# DAUGHTER_SENSOR.net
KiCad netlist of a schematic drawn in EAGLE
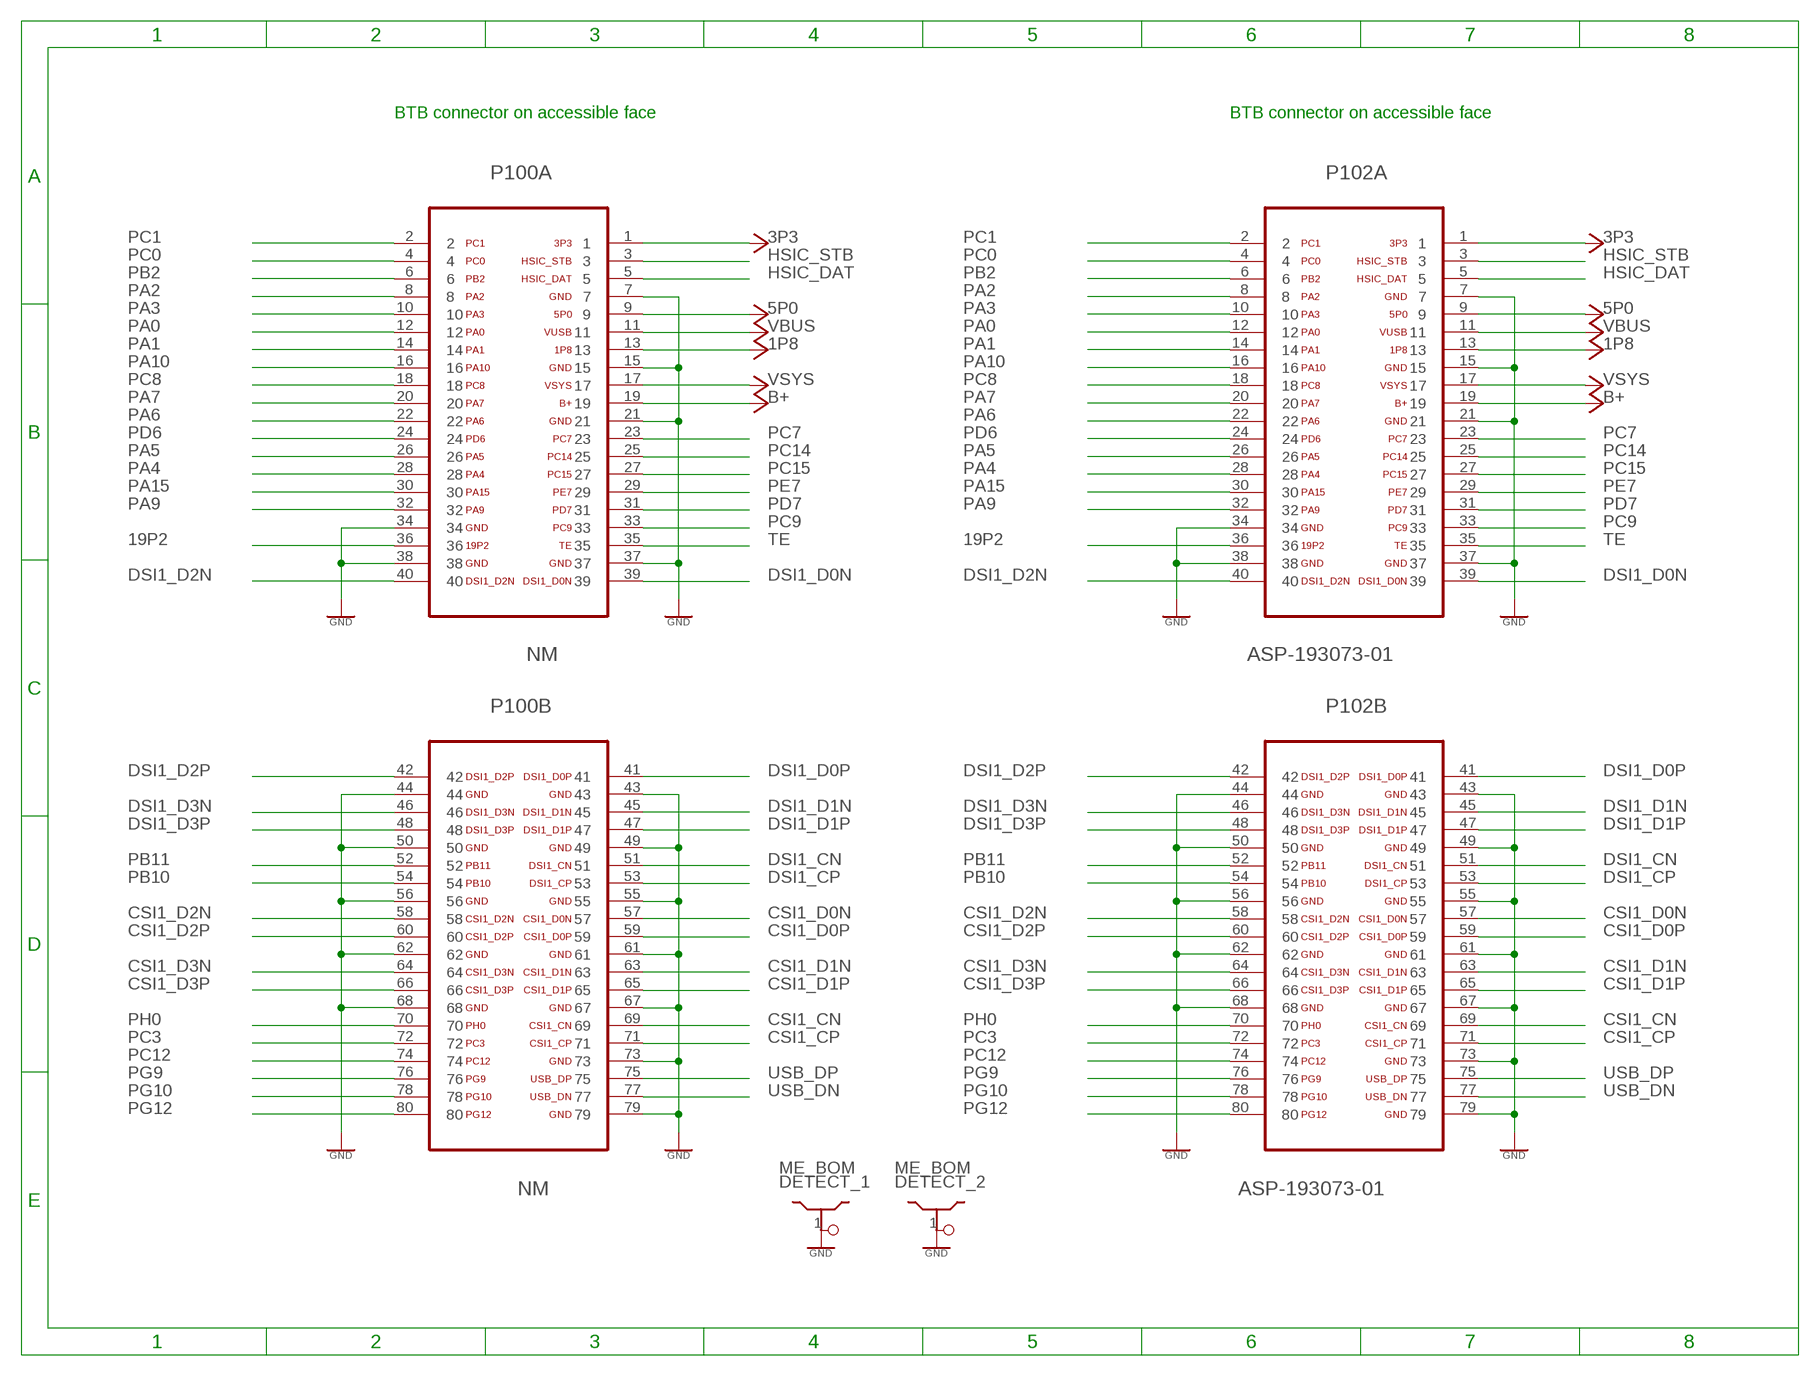
[diagram p0: schematic, sheet 1]
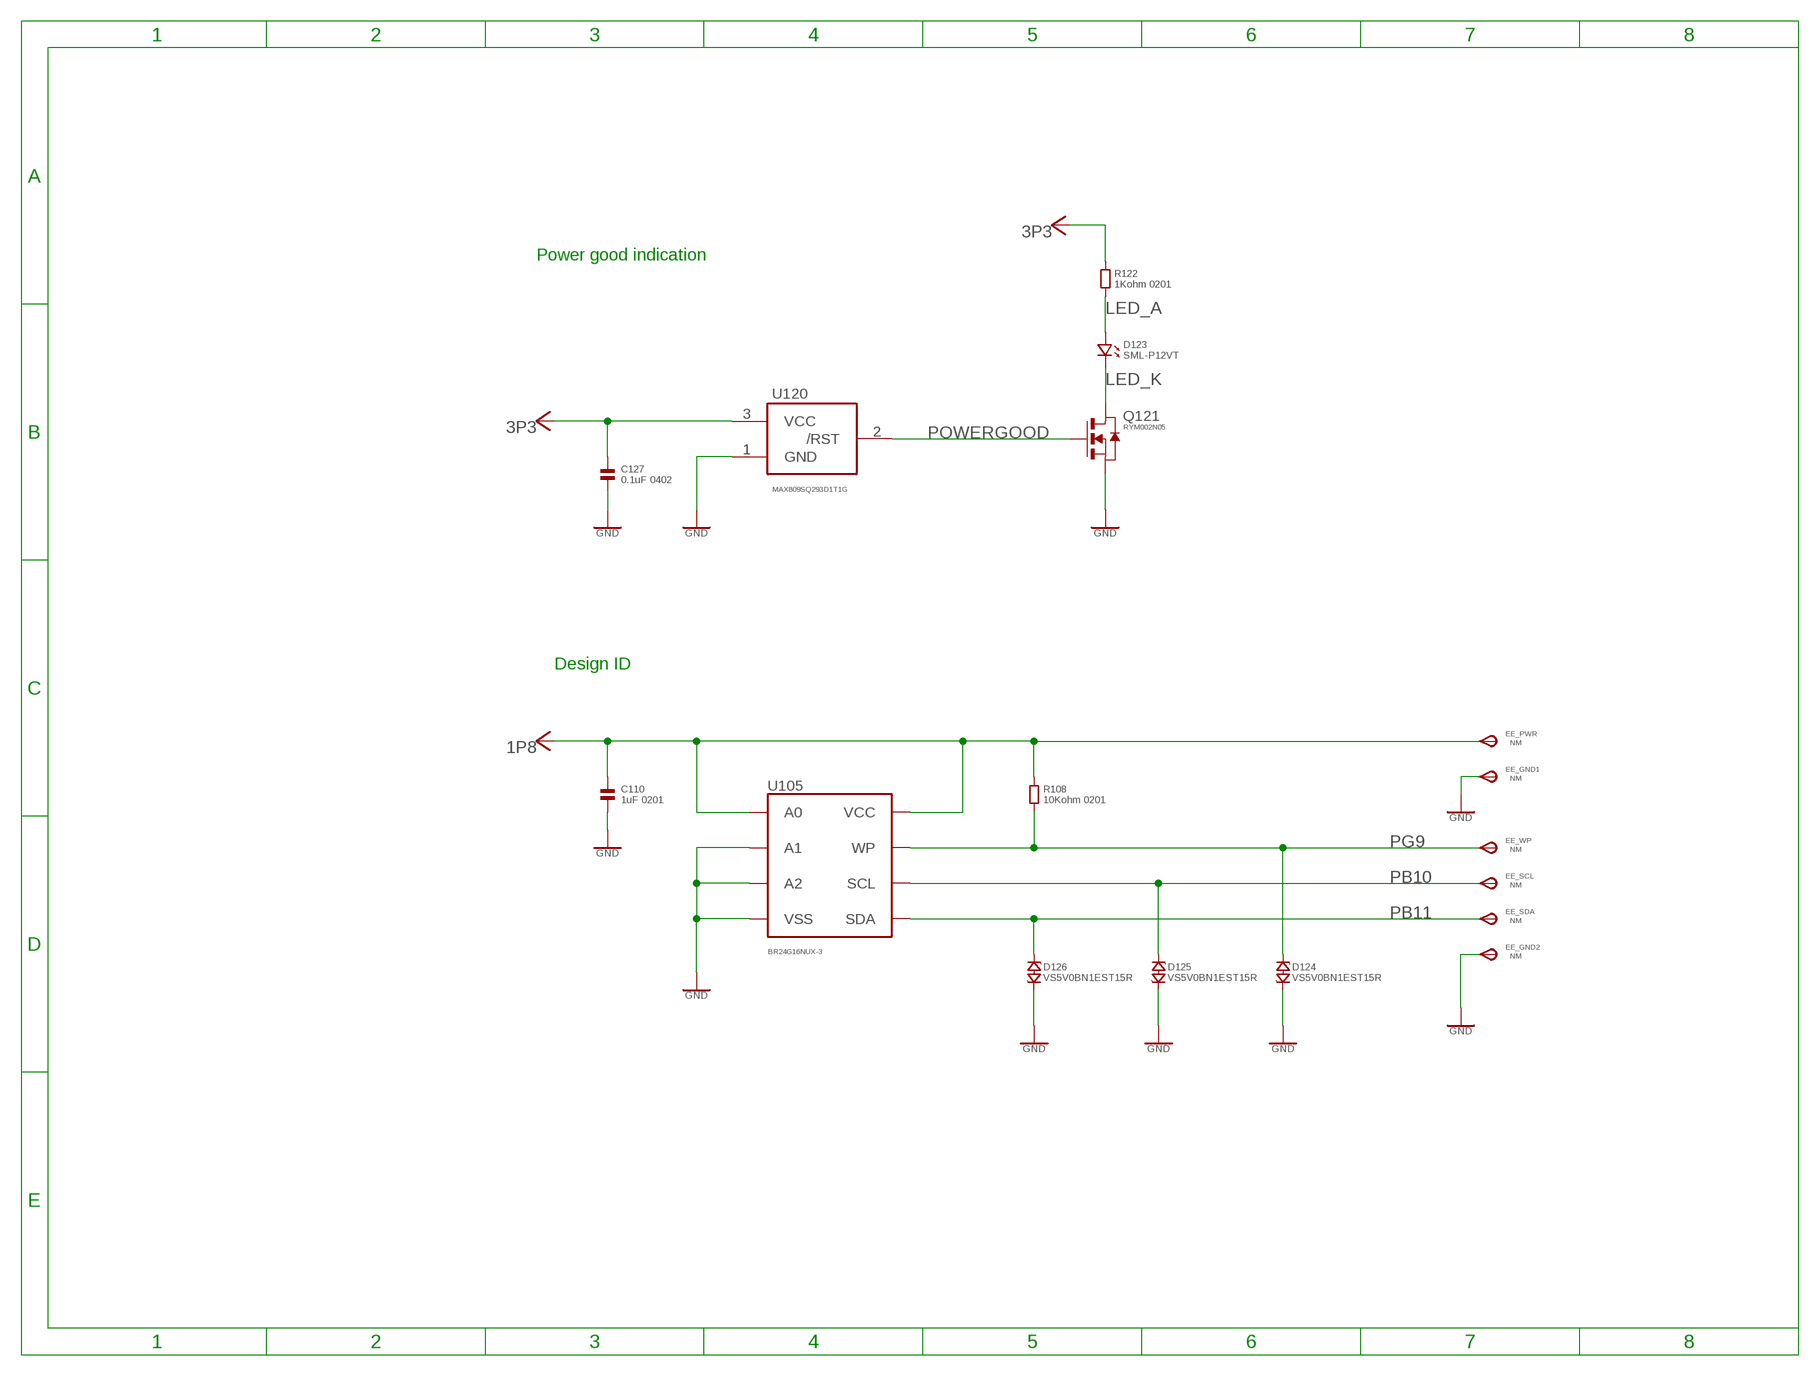
[diagram p1: schematic, sheet 2]
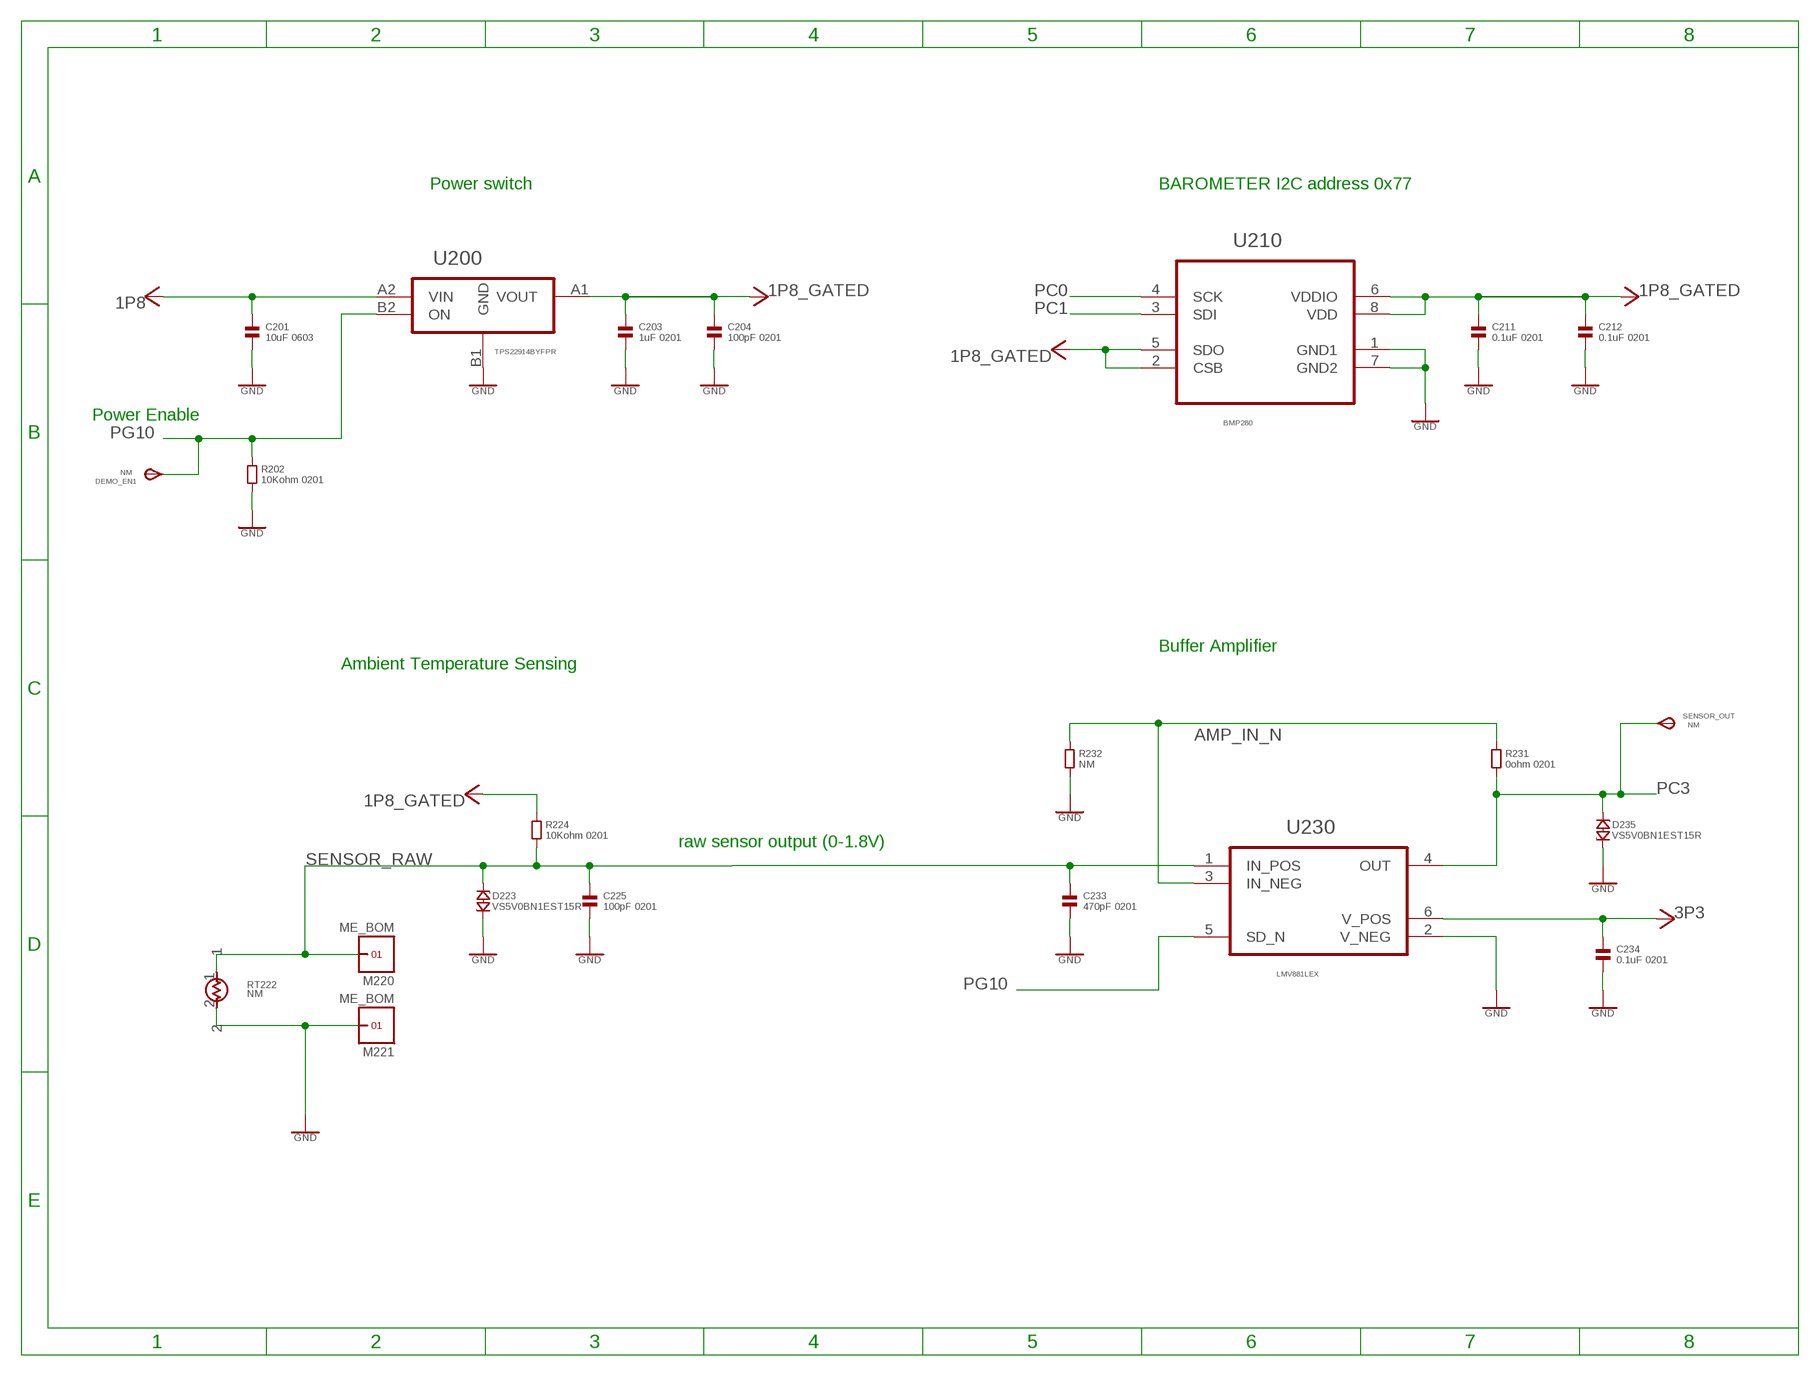
[diagram p2: schematic, sheet 3]

(export (version "E")
  (design (tool "Eeschema 10.0.6"))
  (components
    (comp (ref "C110")
      (value "1uF 0201")
      (footprint "eagle-import:0201")
      (libsource (lib "eagle-import") (part "CAPACITOR.0201"))
    )
    (comp (ref "C127")
      (value "0.1uF 0402")
      (footprint "eagle-import:0402")
      (libsource (lib "eagle-import") (part "CAPACITOR.0402"))
    )
    (comp (ref "D123")
      (value "SML-P12VT")
      (footprint "eagle-import:0503.LED")
      (libsource (lib "eagle-import") (part "LED.0503"))
    )
    (comp (ref "D124")
      (value "VS5V0BN1EST15R")
      (footprint "eagle-import:CHIP_0201")
      (libsource (lib "eagle-import") (part "ESD_VARISTOR.0201"))
    )
    (comp (ref "D125")
      (value "VS5V0BN1EST15R")
      (footprint "eagle-import:CHIP_0201")
      (libsource (lib "eagle-import") (part "ESD_VARISTOR.0201"))
    )
    (comp (ref "D126")
      (value "VS5V0BN1EST15R")
      (footprint "eagle-import:CHIP_0201")
      (libsource (lib "eagle-import") (part "ESD_VARISTOR.0201"))
    )
    (comp (ref "EE_GND1")
      (value "NM")
      (footprint "eagle-import:TP11R")
      (libsource (lib "eagle-import") (part "TPSTP11R"))
    )
    (comp (ref "EE_GND2")
      (value "NM")
      (footprint "eagle-import:TP11R")
      (libsource (lib "eagle-import") (part "TPSTP11R"))
    )
    (comp (ref "EE_PWR")
      (value "NM")
      (footprint "eagle-import:TP11R")
      (libsource (lib "eagle-import") (part "TPSTP11R"))
    )
    (comp (ref "EE_SCL")
      (value "NM")
      (footprint "eagle-import:TP11R")
      (libsource (lib "eagle-import") (part "TPSTP11R"))
    )
    (comp (ref "EE_SDA")
      (value "NM")
      (footprint "eagle-import:TP11R")
      (libsource (lib "eagle-import") (part "TPSTP11R"))
    )
    (comp (ref "EE_WP")
      (value "NM")
      (footprint "eagle-import:TP11R")
      (libsource (lib "eagle-import") (part "TPSTP11R"))
    )
    (comp (ref "Q121")
      (value "RYM002N05")
      (footprint "eagle-import:VMT3")
      (libsource (lib "eagle-import") (part "FET-NRYM002N05"))
    )
    (comp (ref "R108")
      (value "10Kohm 0201")
      (footprint "eagle-import:0201")
      (libsource (lib "eagle-import") (part "RESISTOR.0201"))
    )
    (comp (ref "R122")
      (value "1Kohm 0201")
      (footprint "eagle-import:0201")
      (libsource (lib "eagle-import") (part "RESISTOR.0201"))
    )
    (comp (ref "U105")
      (value "BR24G16NUX-3")
      (footprint "eagle-import:DFN-8")
      (libsource (lib "eagle-import") (part "EEPROMDFN8"))
    )
    (comp (ref "U120")
      (value "MAX809SQ293D1T1G")
      (footprint "eagle-import:SC70-3L")
      (fields (field (name "MPN") "MAX809SQ293D1T1"))
      (libsource (lib "eagle-import") (part "MAX809"))
    )
    (comp (ref "DETECT_1")
      (value "ME_BOM")
      (footprint "eagle-import:PLUG")
      (fields (field (name "MPN") "refer to ME BOM"))
      (libsource (lib "eagle-import") (part "SHIELDDETECT"))
    )
    (comp (ref "DETECT_2")
      (value "ME_BOM")
      (footprint "eagle-import:PLUG")
      (fields (field (name "MPN") "refer to ME BOM"))
      (libsource (lib "eagle-import") (part "SHIELDDETECT"))
    )
    (comp (ref "P100")
      (value "NM")
      (footprint "eagle-import:CLM-140-02-L-D-K_GOLD")
      (fields (field (name "MPN") "CLM-140-02-L-D-K"))
      (libsource (lib "eagle-import") (part "CLM-140-02-L-D-KGOLD"))
    )
    (comp (ref "P102")
      (value "ASP-193073-01")
      (footprint "eagle-import:FTMH-140-02-L-DV-ES-P-TR")
      (fields (field (name "MPN") "ASP-193073-01"))
      (libsource (lib "eagle-import") (part "FTMH-140-02-L-DV-ES-P-TR"))
    )
    (comp (ref "C201")
      (value "10uF 0603")
      (footprint "eagle-import:0603")
      (libsource (lib "eagle-import") (part "CAPACITOR.0603"))
    )
    (comp (ref "C203")
      (value "1uF 0201")
      (footprint "eagle-import:0201")
      (libsource (lib "eagle-import") (part "CAPACITOR.0201"))
    )
    (comp (ref "C204")
      (value "100pF 0201")
      (footprint "eagle-import:0201")
      (libsource (lib "eagle-import") (part "CAPACITOR.0201"))
    )
    (comp (ref "C211")
      (value "0.1uF 0201")
      (footprint "eagle-import:0201")
      (libsource (lib "eagle-import") (part "CAPACITOR.0201"))
    )
    (comp (ref "C212")
      (value "0.1uF 0201")
      (footprint "eagle-import:0201")
      (libsource (lib "eagle-import") (part "CAPACITOR.0201"))
    )
    (comp (ref "C225")
      (value "100pF 0201")
      (footprint "eagle-import:0201")
      (libsource (lib "eagle-import") (part "CAPACITOR.0201"))
    )
    (comp (ref "C233")
      (value "470pF 0201")
      (footprint "eagle-import:0201")
      (libsource (lib "eagle-import") (part "CAPACITOR.0201"))
    )
    (comp (ref "C234")
      (value "0.1uF 0201")
      (footprint "eagle-import:0201")
      (libsource (lib "eagle-import") (part "CAPACITOR.0201"))
    )
    (comp (ref "D223")
      (value "VS5V0BN1EST15R")
      (footprint "eagle-import:CHIP_0201")
      (libsource (lib "eagle-import") (part "ESD_VARISTOR.0201"))
    )
    (comp (ref "D235")
      (value "VS5V0BN1EST15R")
      (footprint "eagle-import:CHIP_0201")
      (libsource (lib "eagle-import") (part "ESD_VARISTOR.0201"))
    )
    (comp (ref "DEMO_EN1")
      (value "NM")
      (footprint "eagle-import:TP11R")
      (libsource (lib "eagle-import") (part "TPSTP11R"))
    )
    (comp (ref "M220")
      (value "ME_BOM")
      (footprint "eagle-import:UNIVERSAL_CONTACT")
      (fields (field (name "MPN") "refer to ME BOM"))
      (libsource (lib "eagle-import") (part "UNVERSA_CONTACT"))
    )
    (comp (ref "M221")
      (value "ME_BOM")
      (footprint "eagle-import:UNIVERSAL_CONTACT")
      (fields (field (name "MPN") "refer to ME BOM"))
      (libsource (lib "eagle-import") (part "UNVERSA_CONTACT"))
    )
    (comp (ref "R202")
      (value "10Kohm 0201")
      (footprint "eagle-import:0201")
      (libsource (lib "eagle-import") (part "RESISTOR.0201"))
    )
    (comp (ref "R224")
      (value "10Kohm 0201")
      (footprint "eagle-import:0201")
      (libsource (lib "eagle-import") (part "RESISTOR.0201"))
    )
    (comp (ref "R231")
      (value "0ohm 0201")
      (footprint "eagle-import:0201")
      (libsource (lib "eagle-import") (part "RESISTOR.0201"))
    )
    (comp (ref "R232")
      (value "NM")
      (footprint "eagle-import:0201")
      (libsource (lib "eagle-import") (part "RESISTOR.0201"))
    )
    (comp (ref "RT222")
      (value "NM")
      (footprint "eagle-import:0201")
      (fields (field (name "MPN") "NCP03XV103XV103E05RL/NTCG0603UH103HT"))
      (libsource (lib "eagle-import") (part "THERMISTOR"))
    )
    (comp (ref "SENSOR_OUT")
      (value "NM")
      (footprint "eagle-import:TP11R")
      (libsource (lib "eagle-import") (part "TPSTP11R"))
    )
    (comp (ref "U200")
      (value "TPS22914BYFPR")
      (footprint "eagle-import:BGA0_75SQ_PS0_4_P4")
      (libsource (lib "eagle-import") (part "TPS22914BYFPR"))
    )
    (comp (ref "U210")
      (value "BMP280")
      (footprint "eagle-import:LGA2X2_5PS0_65_P8")
      (libsource (lib "eagle-import") (part "BMP280"))
    )
    (comp (ref "U230")
      (value "LMV881LEX")
      (footprint "eagle-import:DFN1_5X1PS0_5P6")
      (libsource (lib "eagle-import") (part "LMV881LEX"))
    )
  )
  (nets
    (net (code "1") (name "1P8") (class "Default")
      (node (ref "C110") (pin "1") (pinfunction "1_1") (pintype "bidirectional"))
      (node (ref "C201") (pin "1") (pinfunction "1_1") (pintype "bidirectional"))
      (node (ref "EE_PWR") (pin "TP") (pinfunction "PP_TP") (pintype "input"))
      (node (ref "P100") (pin "13") (pinfunction "13_13") (pintype "passive"))
      (node (ref "P102") (pin "13") (pinfunction "13_13") (pintype "passive"))
      (node (ref "R108") (pin "1") (pinfunction "1_1") (pintype "bidirectional"))
      (node (ref "U105") (pin "P$1") (pinfunction "A0_P$1") (pintype "input"))
      (node (ref "U105") (pin "P$8") (pinfunction "VCC_P$8") (pintype "power_in"))
      (node (ref "U200") (pin "A2") (pinfunction "VIN_A2") (pintype "power_in"))
    )
    (net (code "2") (name "1P8_GATED") (class "Default")
      (node (ref "C203") (pin "1") (pinfunction "1_1") (pintype "bidirectional"))
      (node (ref "C204") (pin "1") (pinfunction "1_1") (pintype "bidirectional"))
      (node (ref "C211") (pin "1") (pinfunction "1_1") (pintype "bidirectional"))
      (node (ref "C212") (pin "1") (pinfunction "1_1") (pintype "bidirectional"))
      (node (ref "R224") (pin "1") (pinfunction "1_1") (pintype "bidirectional"))
      (node (ref "U200") (pin "A1") (pinfunction "VOUT_A1") (pintype "power_in"))
      (node (ref "U210") (pin "2") (pinfunction "CSB_2") (pintype "input"))
      (node (ref "U210") (pin "5") (pinfunction "SDO_5") (pintype "bidirectional"))
      (node (ref "U210") (pin "6") (pinfunction "VDDIO_6") (pintype "power_in"))
      (node (ref "U210") (pin "8") (pinfunction "VDD_8") (pintype "power_in"))
    )
    (net (code "3") (name "3P3") (class "Default")
      (node (ref "C127") (pin "1") (pinfunction "1_1") (pintype "bidirectional"))
      (node (ref "C234") (pin "1") (pinfunction "1_1") (pintype "bidirectional"))
      (node (ref "P100") (pin "1") (pinfunction "1_1") (pintype "passive"))
      (node (ref "P102") (pin "1") (pinfunction "1_1") (pintype "passive"))
      (node (ref "R122") (pin "1") (pinfunction "1_1") (pintype "bidirectional"))
      (node (ref "U120") (pin "3") (pinfunction "VCC_3") (pintype "input"))
      (node (ref "U230") (pin "6") (pinfunction "V_POS_6") (pintype "power_in"))
    )
    (net (code "4") (name "5P0") (class "Default")
      (node (ref "P100") (pin "9") (pinfunction "9_9") (pintype "passive"))
      (node (ref "P102") (pin "9") (pinfunction "9_9") (pintype "passive"))
    )
    (net (code "5") (name "19P2") (class "Default")
      (node (ref "P100") (pin "36") (pinfunction "36_36") (pintype "passive"))
      (node (ref "P102") (pin "36") (pinfunction "36_36") (pintype "passive"))
    )
    (net (code "6") (name "AMP_IN_N") (class "Default")
      (node (ref "R231") (pin "1") (pinfunction "1_1") (pintype "bidirectional"))
      (node (ref "R232") (pin "1") (pinfunction "1_1") (pintype "bidirectional"))
      (node (ref "U230") (pin "3") (pinfunction "IN_NEG_3") (pintype "input"))
    )
    (net (code "7") (name "B+") (class "Default")
      (node (ref "P100") (pin "19") (pinfunction "19_19") (pintype "passive"))
      (node (ref "P102") (pin "19") (pinfunction "19_19") (pintype "passive"))
    )
    (net (code "8") (name "CSI1_CN") (class "Default")
      (node (ref "P100") (pin "69") (pinfunction "69_69") (pintype "passive"))
      (node (ref "P102") (pin "69") (pinfunction "69_69") (pintype "passive"))
    )
    (net (code "9") (name "CSI1_CP") (class "Default")
      (node (ref "P100") (pin "71") (pinfunction "71_71") (pintype "passive"))
      (node (ref "P102") (pin "71") (pinfunction "71_71") (pintype "passive"))
    )
    (net (code "10") (name "CSI1_D0N") (class "Default")
      (node (ref "P100") (pin "57") (pinfunction "57_57") (pintype "passive"))
      (node (ref "P102") (pin "57") (pinfunction "57_57") (pintype "passive"))
    )
    (net (code "11") (name "CSI1_D0P") (class "Default")
      (node (ref "P100") (pin "59") (pinfunction "59_59") (pintype "passive"))
      (node (ref "P102") (pin "59") (pinfunction "59_59") (pintype "passive"))
    )
    (net (code "12") (name "CSI1_D1N") (class "Default")
      (node (ref "P100") (pin "63") (pinfunction "63_63") (pintype "passive"))
      (node (ref "P102") (pin "63") (pinfunction "63_63") (pintype "passive"))
    )
    (net (code "13") (name "CSI1_D1P") (class "Default")
      (node (ref "P100") (pin "65") (pinfunction "65_65") (pintype "passive"))
      (node (ref "P102") (pin "65") (pinfunction "65_65") (pintype "passive"))
    )
    (net (code "14") (name "CSI1_D2N") (class "Default")
      (node (ref "P100") (pin "58") (pinfunction "58_58") (pintype "passive"))
      (node (ref "P102") (pin "58") (pinfunction "58_58") (pintype "passive"))
    )
    (net (code "15") (name "CSI1_D2P") (class "Default")
      (node (ref "P100") (pin "60") (pinfunction "60_60") (pintype "passive"))
      (node (ref "P102") (pin "60") (pinfunction "60_60") (pintype "passive"))
    )
    (net (code "16") (name "CSI1_D3N") (class "Default")
      (node (ref "P100") (pin "64") (pinfunction "64_64") (pintype "passive"))
      (node (ref "P102") (pin "64") (pinfunction "64_64") (pintype "passive"))
    )
    (net (code "17") (name "CSI1_D3P") (class "Default")
      (node (ref "P100") (pin "66") (pinfunction "66_66") (pintype "passive"))
      (node (ref "P102") (pin "66") (pinfunction "66_66") (pintype "passive"))
    )
    (net (code "18") (name "DSI1_CN") (class "Default")
      (node (ref "P100") (pin "51") (pinfunction "51_51") (pintype "passive"))
      (node (ref "P102") (pin "51") (pinfunction "51_51") (pintype "passive"))
    )
    (net (code "19") (name "DSI1_CP") (class "Default")
      (node (ref "P100") (pin "53") (pinfunction "53_53") (pintype "passive"))
      (node (ref "P102") (pin "53") (pinfunction "53_53") (pintype "passive"))
    )
    (net (code "20") (name "DSI1_D0N") (class "Default")
      (node (ref "P100") (pin "39") (pinfunction "39_39") (pintype "passive"))
      (node (ref "P102") (pin "39") (pinfunction "39_39") (pintype "passive"))
    )
    (net (code "21") (name "DSI1_D0P") (class "Default")
      (node (ref "P100") (pin "41") (pinfunction "41_41") (pintype "passive"))
      (node (ref "P102") (pin "41") (pinfunction "41_41") (pintype "passive"))
    )
    (net (code "22") (name "DSI1_D1N") (class "Default")
      (node (ref "P100") (pin "45") (pinfunction "45_45") (pintype "passive"))
      (node (ref "P102") (pin "45") (pinfunction "45_45") (pintype "passive"))
    )
    (net (code "23") (name "DSI1_D1P") (class "Default")
      (node (ref "P100") (pin "47") (pinfunction "47_47") (pintype "passive"))
      (node (ref "P102") (pin "47") (pinfunction "47_47") (pintype "passive"))
    )
    (net (code "24") (name "DSI1_D2N") (class "Default")
      (node (ref "P100") (pin "40") (pinfunction "40_40") (pintype "passive"))
      (node (ref "P102") (pin "40") (pinfunction "40_40") (pintype "passive"))
    )
    (net (code "25") (name "DSI1_D2P") (class "Default")
      (node (ref "P100") (pin "42") (pinfunction "42_42") (pintype "passive"))
      (node (ref "P102") (pin "42") (pinfunction "42_42") (pintype "passive"))
    )
    (net (code "26") (name "DSI1_D3N") (class "Default")
      (node (ref "P100") (pin "46") (pinfunction "46_46") (pintype "passive"))
      (node (ref "P102") (pin "46") (pinfunction "46_46") (pintype "passive"))
    )
    (net (code "27") (name "DSI1_D3P") (class "Default")
      (node (ref "P100") (pin "48") (pinfunction "48_48") (pintype "passive"))
      (node (ref "P102") (pin "48") (pinfunction "48_48") (pintype "passive"))
    )
    (net (code "28") (name "GND") (class "Default")
      (node (ref "C110") (pin "2") (pinfunction "2_2") (pintype "bidirectional"))
      (node (ref "C127") (pin "2") (pinfunction "2_2") (pintype "bidirectional"))
      (node (ref "C201") (pin "2") (pinfunction "2_2") (pintype "bidirectional"))
      (node (ref "C203") (pin "2") (pinfunction "2_2") (pintype "bidirectional"))
      (node (ref "C204") (pin "2") (pinfunction "2_2") (pintype "bidirectional"))
      (node (ref "C211") (pin "2") (pinfunction "2_2") (pintype "bidirectional"))
      (node (ref "C212") (pin "2") (pinfunction "2_2") (pintype "bidirectional"))
      (node (ref "C225") (pin "2") (pinfunction "2_2") (pintype "bidirectional"))
      (node (ref "C233") (pin "2") (pinfunction "2_2") (pintype "bidirectional"))
      (node (ref "C234") (pin "2") (pinfunction "2_2") (pintype "bidirectional"))
      (node (ref "D124") (pin "P$2") (pinfunction "2_P$2") (pintype "bidirectional"))
      (node (ref "D125") (pin "P$2") (pinfunction "2_P$2") (pintype "bidirectional"))
      (node (ref "D126") (pin "P$2") (pinfunction "2_P$2") (pintype "bidirectional"))
      (node (ref "D223") (pin "P$2") (pinfunction "2_P$2") (pintype "bidirectional"))
      (node (ref "D235") (pin "P$2") (pinfunction "2_P$2") (pintype "bidirectional"))
      (node (ref "DETECT_1") (pin "1") (pinfunction "1_1") (pintype "passive"))
      (node (ref "DETECT_2") (pin "1") (pinfunction "1_1") (pintype "passive"))
      (node (ref "EE_GND1") (pin "TP") (pinfunction "PP_TP") (pintype "input"))
      (node (ref "EE_GND2") (pin "TP") (pinfunction "PP_TP") (pintype "input"))
      (node (ref "M221") (pin "G1") (pinfunction "1_G1") (pintype "bidirectional"))
      (node (ref "P100") (pin "15") (pinfunction "15_15") (pintype "passive"))
      (node (ref "P100") (pin "21") (pinfunction "21_21") (pintype "passive"))
      (node (ref "P100") (pin "34") (pinfunction "34_34") (pintype "passive"))
      (node (ref "P100") (pin "37") (pinfunction "37_37") (pintype "passive"))
      (node (ref "P100") (pin "38") (pinfunction "38_38") (pintype "passive"))
      (node (ref "P100") (pin "43") (pinfunction "43_43") (pintype "passive"))
      (node (ref "P100") (pin "44") (pinfunction "44_44") (pintype "passive"))
      (node (ref "P100") (pin "49") (pinfunction "49_49") (pintype "passive"))
      (node (ref "P100") (pin "50") (pinfunction "50_50") (pintype "passive"))
      (node (ref "P100") (pin "55") (pinfunction "55_55") (pintype "passive"))
      (node (ref "P100") (pin "56") (pinfunction "56_56") (pintype "passive"))
      (node (ref "P100") (pin "61") (pinfunction "61_61") (pintype "passive"))
      (node (ref "P100") (pin "62") (pinfunction "62_62") (pintype "passive"))
      (node (ref "P100") (pin "67") (pinfunction "67_67") (pintype "passive"))
      (node (ref "P100") (pin "68") (pinfunction "68_68") (pintype "passive"))
      (node (ref "P100") (pin "7") (pinfunction "7_7") (pintype "passive"))
      (node (ref "P100") (pin "73") (pinfunction "73_73") (pintype "passive"))
      (node (ref "P100") (pin "79") (pinfunction "79_79") (pintype "passive"))
      (node (ref "P102") (pin "15") (pinfunction "15_15") (pintype "passive"))
      (node (ref "P102") (pin "21") (pinfunction "21_21") (pintype "passive"))
      (node (ref "P102") (pin "34") (pinfunction "34_34") (pintype "passive"))
      (node (ref "P102") (pin "37") (pinfunction "37_37") (pintype "passive"))
      (node (ref "P102") (pin "38") (pinfunction "38_38") (pintype "passive"))
      (node (ref "P102") (pin "43") (pinfunction "43_43") (pintype "passive"))
      (node (ref "P102") (pin "44") (pinfunction "44_44") (pintype "passive"))
      (node (ref "P102") (pin "49") (pinfunction "49_49") (pintype "passive"))
      (node (ref "P102") (pin "50") (pinfunction "50_50") (pintype "passive"))
      (node (ref "P102") (pin "55") (pinfunction "55_55") (pintype "passive"))
      (node (ref "P102") (pin "56") (pinfunction "56_56") (pintype "passive"))
      (node (ref "P102") (pin "61") (pinfunction "61_61") (pintype "passive"))
      (node (ref "P102") (pin "62") (pinfunction "62_62") (pintype "passive"))
      (node (ref "P102") (pin "67") (pinfunction "67_67") (pintype "passive"))
      (node (ref "P102") (pin "68") (pinfunction "68_68") (pintype "passive"))
      (node (ref "P102") (pin "7") (pinfunction "7_7") (pintype "passive"))
      (node (ref "P102") (pin "73") (pinfunction "73_73") (pintype "passive"))
      (node (ref "P102") (pin "79") (pinfunction "79_79") (pintype "passive"))
      (node (ref "Q121") (pin "2") (pinfunction "S_2") (pintype "passive"))
      (node (ref "R202") (pin "2") (pinfunction "2_2") (pintype "bidirectional"))
      (node (ref "R232") (pin "2") (pinfunction "2_2") (pintype "bidirectional"))
      (node (ref "RT222") (pin "2") (pinfunction "2_2") (pintype "bidirectional"))
      (node (ref "U105") (pin "P$2") (pinfunction "A1_P$2") (pintype "input"))
      (node (ref "U105") (pin "P$3") (pinfunction "A2_P$3") (pintype "input"))
      (node (ref "U105") (pin "P$4") (pinfunction "VSS_P$4") (pintype "power_in"))
      (node (ref "U105") (pin "P$9") (pinfunction "VSS_P$9") (pintype "power_in"))
      (node (ref "U120") (pin "1") (pinfunction "GND_1") (pintype "power_in"))
      (node (ref "U200") (pin "B1") (pinfunction "GND_B1") (pintype "power_in"))
      (node (ref "U210") (pin "1") (pinfunction "GND1_1") (pintype "power_in"))
      (node (ref "U210") (pin "7") (pinfunction "GND2_7") (pintype "power_in"))
      (node (ref "U230") (pin "2") (pinfunction "V_NEG_2") (pintype "power_in"))
    )
    (net (code "29") (name "HSIC_DAT") (class "Default")
      (node (ref "P100") (pin "5") (pinfunction "5_5") (pintype "passive"))
      (node (ref "P102") (pin "5") (pinfunction "5_5") (pintype "passive"))
    )
    (net (code "30") (name "HSIC_STB") (class "Default")
      (node (ref "P100") (pin "3") (pinfunction "3_3") (pintype "passive"))
      (node (ref "P102") (pin "3") (pinfunction "3_3") (pintype "passive"))
    )
    (net (code "31") (name "LED_A") (class "Default")
      (node (ref "D123") (pin "P$1") (pinfunction "1_P$1") (pintype "bidirectional"))
      (node (ref "R122") (pin "2") (pinfunction "2_2") (pintype "bidirectional"))
    )
    (net (code "32") (name "LED_K") (class "Default")
      (node (ref "D123") (pin "P$2") (pinfunction "2_P$2") (pintype "bidirectional"))
      (node (ref "Q121") (pin "3") (pinfunction "D_3") (pintype "passive"))
    )
    (net (code "33") (name "PA0") (class "Default")
      (node (ref "P100") (pin "12") (pinfunction "12_12") (pintype "passive"))
      (node (ref "P102") (pin "12") (pinfunction "12_12") (pintype "passive"))
    )
    (net (code "34") (name "PA1") (class "Default")
      (node (ref "P100") (pin "14") (pinfunction "14_14") (pintype "passive"))
      (node (ref "P102") (pin "14") (pinfunction "14_14") (pintype "passive"))
    )
    (net (code "35") (name "PA2") (class "Default")
      (node (ref "P100") (pin "8") (pinfunction "8_8") (pintype "passive"))
      (node (ref "P102") (pin "8") (pinfunction "8_8") (pintype "passive"))
    )
    (net (code "36") (name "PA3") (class "Default")
      (node (ref "P100") (pin "10") (pinfunction "10_10") (pintype "passive"))
      (node (ref "P102") (pin "10") (pinfunction "10_10") (pintype "passive"))
    )
    (net (code "37") (name "PA4") (class "Default")
      (node (ref "P100") (pin "28") (pinfunction "28_28") (pintype "passive"))
      (node (ref "P102") (pin "28") (pinfunction "28_28") (pintype "passive"))
    )
    (net (code "38") (name "PA5") (class "Default")
      (node (ref "P100") (pin "26") (pinfunction "26_26") (pintype "passive"))
      (node (ref "P102") (pin "26") (pinfunction "26_26") (pintype "passive"))
    )
    (net (code "39") (name "PA6") (class "Default")
      (node (ref "P100") (pin "22") (pinfunction "22_22") (pintype "passive"))
      (node (ref "P102") (pin "22") (pinfunction "22_22") (pintype "passive"))
    )
    (net (code "40") (name "PA7") (class "Default")
      (node (ref "P100") (pin "20") (pinfunction "20_20") (pintype "passive"))
      (node (ref "P102") (pin "20") (pinfunction "20_20") (pintype "passive"))
    )
    (net (code "41") (name "PA9") (class "Default")
      (node (ref "P100") (pin "32") (pinfunction "32_32") (pintype "passive"))
      (node (ref "P102") (pin "32") (pinfunction "32_32") (pintype "passive"))
    )
    (net (code "42") (name "PA10") (class "Default")
      (node (ref "P100") (pin "16") (pinfunction "16_16") (pintype "passive"))
      (node (ref "P102") (pin "16") (pinfunction "16_16") (pintype "passive"))
    )
    (net (code "43") (name "PA15") (class "Default")
      (node (ref "P100") (pin "30") (pinfunction "30_30") (pintype "passive"))
      (node (ref "P102") (pin "30") (pinfunction "30_30") (pintype "passive"))
    )
    (net (code "44") (name "PB2") (class "Default")
      (node (ref "P100") (pin "6") (pinfunction "6_6") (pintype "passive"))
      (node (ref "P102") (pin "6") (pinfunction "6_6") (pintype "passive"))
    )
    (net (code "45") (name "PB10") (class "Default")
      (node (ref "D125") (pin "P$1") (pinfunction "1_P$1") (pintype "bidirectional"))
      (node (ref "EE_SCL") (pin "TP") (pinfunction "PP_TP") (pintype "input"))
      (node (ref "P100") (pin "54") (pinfunction "54_54") (pintype "passive"))
      (node (ref "P102") (pin "54") (pinfunction "54_54") (pintype "passive"))
      (node (ref "U105") (pin "P$6") (pinfunction "SCL_P$6") (pintype "input"))
    )
    (net (code "46") (name "PB11") (class "Default")
      (node (ref "D126") (pin "P$1") (pinfunction "1_P$1") (pintype "bidirectional"))
      (node (ref "EE_SDA") (pin "TP") (pinfunction "PP_TP") (pintype "input"))
      (node (ref "P100") (pin "52") (pinfunction "52_52") (pintype "passive"))
      (node (ref "P102") (pin "52") (pinfunction "52_52") (pintype "passive"))
      (node (ref "U105") (pin "P$5") (pinfunction "SDA_P$5") (pintype "bidirectional"))
    )
    (net (code "47") (name "PC0") (class "Default")
      (node (ref "P100") (pin "4") (pinfunction "4_4") (pintype "passive"))
      (node (ref "P102") (pin "4") (pinfunction "4_4") (pintype "passive"))
      (node (ref "U210") (pin "4") (pinfunction "SCK_4") (pintype "input"))
    )
    (net (code "48") (name "PC1") (class "Default")
      (node (ref "P100") (pin "2") (pinfunction "2_2") (pintype "passive"))
      (node (ref "P102") (pin "2") (pinfunction "2_2") (pintype "passive"))
      (node (ref "U210") (pin "3") (pinfunction "SDI_3") (pintype "bidirectional"))
    )
    (net (code "49") (name "PC3") (class "Default")
      (node (ref "D235") (pin "P$1") (pinfunction "1_P$1") (pintype "bidirectional"))
      (node (ref "P100") (pin "72") (pinfunction "72_72") (pintype "passive"))
      (node (ref "P102") (pin "72") (pinfunction "72_72") (pintype "passive"))
      (node (ref "R231") (pin "2") (pinfunction "2_2") (pintype "bidirectional"))
      (node (ref "SENSOR_OUT") (pin "TP") (pinfunction "PP_TP") (pintype "input"))
      (node (ref "U230") (pin "4") (pinfunction "OUT_4") (pintype "output"))
    )
    (net (code "50") (name "PC7") (class "Default")
      (node (ref "P100") (pin "23") (pinfunction "23_23") (pintype "passive"))
      (node (ref "P102") (pin "23") (pinfunction "23_23") (pintype "passive"))
    )
    (net (code "51") (name "PC8") (class "Default")
      (node (ref "P100") (pin "18") (pinfunction "18_18") (pintype "passive"))
      (node (ref "P102") (pin "18") (pinfunction "18_18") (pintype "passive"))
    )
    (net (code "52") (name "PC9") (class "Default")
      (node (ref "P100") (pin "33") (pinfunction "33_33") (pintype "passive"))
      (node (ref "P102") (pin "33") (pinfunction "33_33") (pintype "passive"))
    )
    (net (code "53") (name "PC12") (class "Default")
      (node (ref "P100") (pin "74") (pinfunction "74_74") (pintype "passive"))
      (node (ref "P102") (pin "74") (pinfunction "74_74") (pintype "passive"))
    )
    (net (code "54") (name "PC14") (class "Default")
      (node (ref "P100") (pin "25") (pinfunction "25_25") (pintype "passive"))
      (node (ref "P102") (pin "25") (pinfunction "25_25") (pintype "passive"))
    )
    (net (code "55") (name "PC15") (class "Default")
      (node (ref "P100") (pin "27") (pinfunction "27_27") (pintype "passive"))
      (node (ref "P102") (pin "27") (pinfunction "27_27") (pintype "passive"))
    )
    (net (code "56") (name "PD6") (class "Default")
      (node (ref "P100") (pin "24") (pinfunction "24_24") (pintype "passive"))
      (node (ref "P102") (pin "24") (pinfunction "24_24") (pintype "passive"))
    )
    (net (code "57") (name "PD7") (class "Default")
      (node (ref "P100") (pin "31") (pinfunction "31_31") (pintype "passive"))
      (node (ref "P102") (pin "31") (pinfunction "31_31") (pintype "passive"))
    )
    (net (code "58") (name "PE7") (class "Default")
      (node (ref "P100") (pin "29") (pinfunction "29_29") (pintype "passive"))
      (node (ref "P102") (pin "29") (pinfunction "29_29") (pintype "passive"))
    )
    (net (code "59") (name "PG9") (class "Default")
      (node (ref "D124") (pin "P$1") (pinfunction "1_P$1") (pintype "bidirectional"))
      (node (ref "EE_WP") (pin "TP") (pinfunction "PP_TP") (pintype "input"))
      (node (ref "P100") (pin "76") (pinfunction "76_76") (pintype "passive"))
      (node (ref "P102") (pin "76") (pinfunction "76_76") (pintype "passive"))
      (node (ref "R108") (pin "2") (pinfunction "2_2") (pintype "bidirectional"))
      (node (ref "U105") (pin "P$7") (pinfunction "WP_P$7") (pintype "input"))
    )
    (net (code "60") (name "PG10") (class "Default")
      (node (ref "DEMO_EN1") (pin "TP") (pinfunction "PP_TP") (pintype "input"))
      (node (ref "P100") (pin "78") (pinfunction "78_78") (pintype "passive"))
      (node (ref "P102") (pin "78") (pinfunction "78_78") (pintype "passive"))
      (node (ref "R202") (pin "1") (pinfunction "1_1") (pintype "bidirectional"))
      (node (ref "U200") (pin "B2") (pinfunction "ON_B2") (pintype "input"))
      (node (ref "U230") (pin "5") (pinfunction "SD_N_5") (pintype "input"))
    )
    (net (code "61") (name "PG12") (class "Default")
      (node (ref "P100") (pin "80") (pinfunction "80_80") (pintype "passive"))
      (node (ref "P102") (pin "80") (pinfunction "80_80") (pintype "passive"))
    )
    (net (code "62") (name "PH0") (class "Default")
      (node (ref "P100") (pin "70") (pinfunction "70_70") (pintype "passive"))
      (node (ref "P102") (pin "70") (pinfunction "70_70") (pintype "passive"))
    )
    (net (code "63") (name "POWERGOOD") (class "Default")
      (node (ref "Q121") (pin "1") (pinfunction "G_1") (pintype "passive"))
      (node (ref "U120") (pin "2") (pinfunction "/RST_2") (pintype "output"))
    )
    (net (code "64") (name "SENSOR_RAW") (class "Default")
      (node (ref "C225") (pin "1") (pinfunction "1_1") (pintype "bidirectional"))
      (node (ref "C233") (pin "1") (pinfunction "1_1") (pintype "bidirectional"))
      (node (ref "D223") (pin "P$1") (pinfunction "1_P$1") (pintype "bidirectional"))
      (node (ref "M220") (pin "G1") (pinfunction "1_G1") (pintype "bidirectional"))
      (node (ref "R224") (pin "2") (pinfunction "2_2") (pintype "bidirectional"))
      (node (ref "RT222") (pin "1") (pinfunction "1_1") (pintype "bidirectional"))
      (node (ref "U230") (pin "1") (pinfunction "IN_POS_1") (pintype "input"))
    )
    (net (code "65") (name "TE") (class "Default")
      (node (ref "P100") (pin "35") (pinfunction "35_35") (pintype "passive"))
      (node (ref "P102") (pin "35") (pinfunction "35_35") (pintype "passive"))
    )
    (net (code "66") (name "USB_DN") (class "Default")
      (node (ref "P100") (pin "77") (pinfunction "77_77") (pintype "passive"))
      (node (ref "P102") (pin "77") (pinfunction "77_77") (pintype "passive"))
    )
    (net (code "67") (name "USB_DP") (class "Default")
      (node (ref "P100") (pin "75") (pinfunction "75_75") (pintype "passive"))
      (node (ref "P102") (pin "75") (pinfunction "75_75") (pintype "passive"))
    )
    (net (code "68") (name "VBUS") (class "Default")
      (node (ref "P100") (pin "11") (pinfunction "11_11") (pintype "passive"))
      (node (ref "P102") (pin "11") (pinfunction "11_11") (pintype "passive"))
    )
    (net (code "69") (name "VSYS") (class "Default")
      (node (ref "P100") (pin "17") (pinfunction "17_17") (pintype "passive"))
      (node (ref "P102") (pin "17") (pinfunction "17_17") (pintype "passive"))
    )
  )
)
